# LCD.net
KiCad netlist of a schematic drawn in Altium Designer
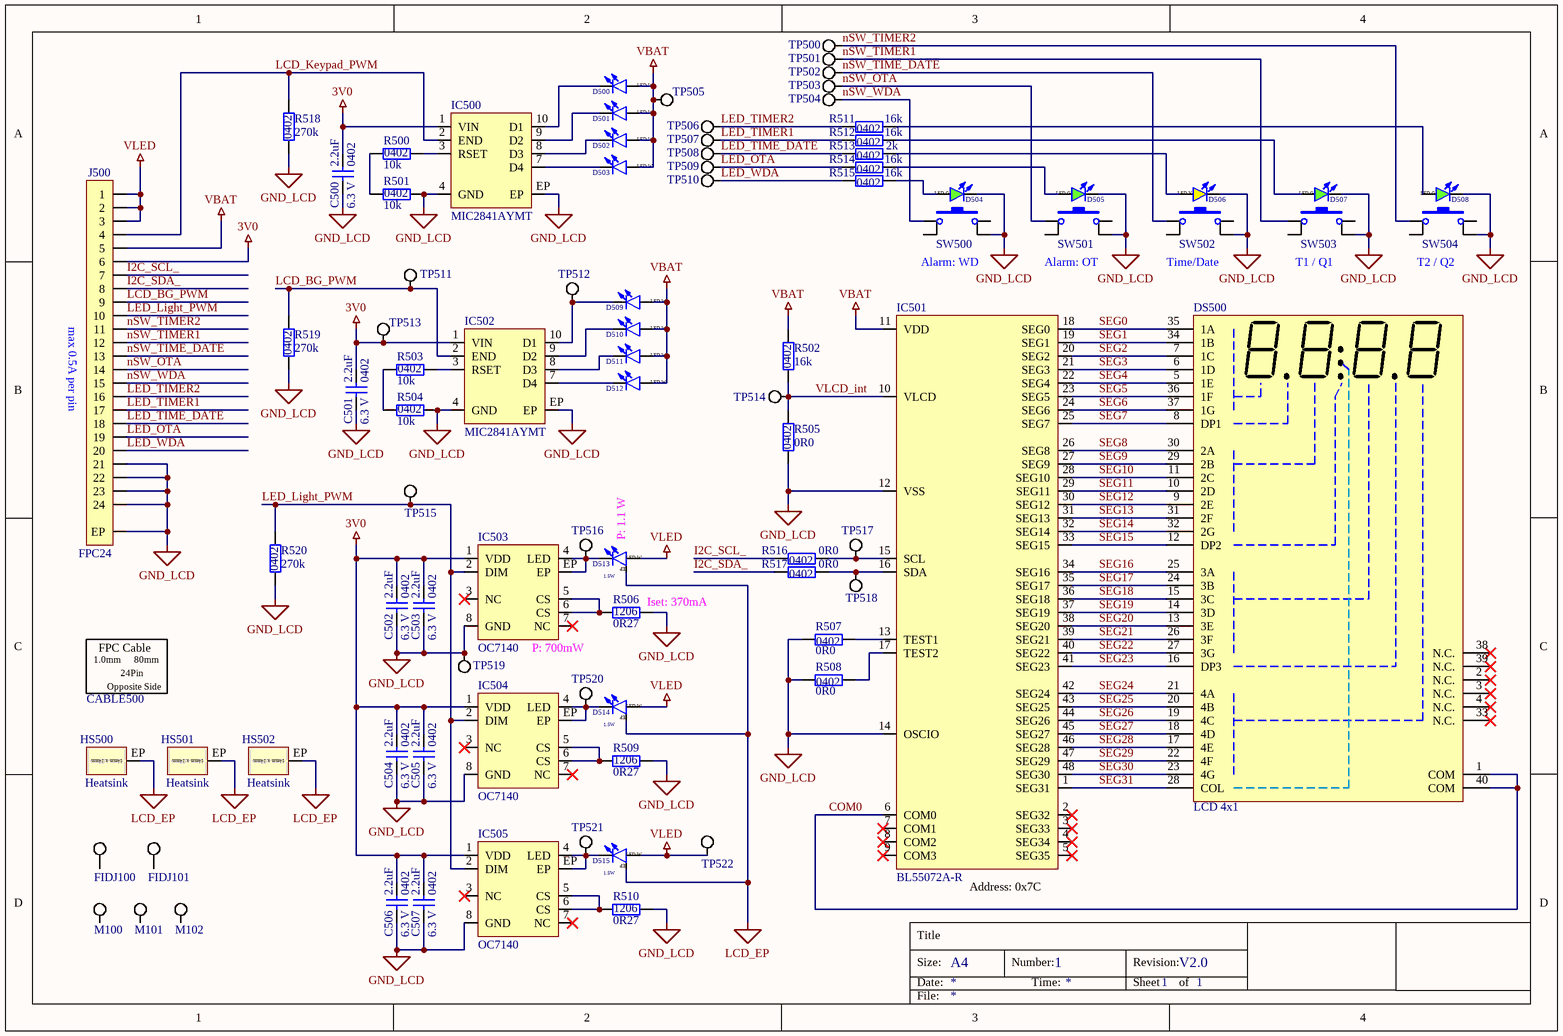
[diagram p0: LCD.SchDoc]

(export (version "E")
  (design (tool "Eeschema 10.0.6"))
  (components
    (comp (ref "C500")
      (value "C 2.2uF 0402 6.3V")
      (footprint "0402")
      (description "CAP CER 2.2UF 6.3V X6T 0402")
      (fields
        (field (name "MANUFACTURER") "Murata Electronics")
        (field (name "MANUFACTURER PART NUMBER") "GRM155D80J225ME95D")
        (field (name "CAPACITANCE") "2.2uF")
        (field (name "VOLTAGE") "6.3 V")
      )
      (libsource (lib "CS_Part_Library") (part "CAP_2.2uF_6V3_0402"))
    )
    (comp (ref "C501")
      (value "C 2.2uF 0402 6.3V")
      (footprint "0402")
      (description "CAP CER 2.2UF 6.3V X6T 0402")
      (fields
        (field (name "MANUFACTURER") "Murata Electronics")
        (field (name "MANUFACTURER PART NUMBER") "GRM155D80J225ME95D")
        (field (name "CAPACITANCE") "2.2uF")
        (field (name "VOLTAGE") "6.3 V")
      )
      (libsource (lib "CS_Part_Library") (part "CAP_2.2uF_6V3_0402"))
    )
    (comp (ref "C502")
      (value "C 2.2uF 0402 6.3V")
      (footprint "0402")
      (description "CAP CER 2.2UF 6.3V X6T 0402")
      (fields
        (field (name "MANUFACTURER") "Murata Electronics")
        (field (name "MANUFACTURER PART NUMBER") "GRM155D80J225ME95D")
        (field (name "CAPACITANCE") "2.2uF")
        (field (name "VOLTAGE") "6.3 V")
      )
      (libsource (lib "CS_Part_Library") (part "CAP_2.2uF_6V3_0402"))
    )
    (comp (ref "C503")
      (value "C 2.2uF 0402 6.3V")
      (footprint "0402")
      (description "CAP CER 2.2UF 6.3V X6T 0402")
      (fields
        (field (name "MANUFACTURER") "Murata Electronics")
        (field (name "MANUFACTURER PART NUMBER") "GRM155D80J225ME95D")
        (field (name "CAPACITANCE") "2.2uF")
        (field (name "VOLTAGE") "6.3 V")
      )
      (libsource (lib "CS_Part_Library") (part "CAP_2.2uF_6V3_0402"))
    )
    (comp (ref "C504")
      (value "C 2.2uF 0402 6.3V")
      (footprint "0402")
      (description "CAP CER 2.2UF 6.3V X6T 0402")
      (fields
        (field (name "MANUFACTURER") "Murata Electronics")
        (field (name "MANUFACTURER PART NUMBER") "GRM155D80J225ME95D")
        (field (name "CAPACITANCE") "2.2uF")
        (field (name "VOLTAGE") "6.3 V")
      )
      (libsource (lib "CS_Part_Library") (part "CAP_2.2uF_6V3_0402"))
    )
    (comp (ref "C505")
      (value "C 2.2uF 0402 6.3V")
      (footprint "0402")
      (description "CAP CER 2.2UF 6.3V X6T 0402")
      (fields
        (field (name "MANUFACTURER") "Murata Electronics")
        (field (name "MANUFACTURER PART NUMBER") "GRM155D80J225ME95D")
        (field (name "CAPACITANCE") "2.2uF")
        (field (name "VOLTAGE") "6.3 V")
      )
      (libsource (lib "CS_Part_Library") (part "CAP_2.2uF_6V3_0402"))
    )
    (comp (ref "C506")
      (value "C 2.2uF 0402 6.3V")
      (footprint "0402")
      (description "CAP CER 2.2UF 6.3V X6T 0402")
      (fields
        (field (name "MANUFACTURER") "Murata Electronics")
        (field (name "MANUFACTURER PART NUMBER") "GRM155D80J225ME95D")
        (field (name "CAPACITANCE") "2.2uF")
        (field (name "VOLTAGE") "6.3 V")
      )
      (libsource (lib "CS_Part_Library") (part "CAP_2.2uF_6V3_0402"))
    )
    (comp (ref "C507")
      (value "C 2.2uF 0402 6.3V")
      (footprint "0402")
      (description "CAP CER 2.2UF 6.3V X6T 0402")
      (fields
        (field (name "MANUFACTURER") "Murata Electronics")
        (field (name "MANUFACTURER PART NUMBER") "GRM155D80J225ME95D")
        (field (name "CAPACITANCE") "2.2uF")
        (field (name "VOLTAGE") "6.3 V")
      )
      (libsource (lib "CS_Part_Library") (part "CAP_2.2uF_6V3_0402"))
    )
    (comp (ref "CABLE500")
      (value "FPC24p80mm")
      (description "FPC Cable 1mm Pitch 24Pin 80mm Opposite Sides")
      (fields
        (field (name "MANUFACTURER") "LX")
        (field (name "MANUFACTURER PART NUMBER") "C50299")
        (field (name "PITCH") "1.0mm")
        (field (name "LENGTH") "80mm")
        (field (name "MODE") "Opposite Side")
        (field (name "NOOFPINS") "24Pin")
      )
      (libsource (lib "Symbols") (part "CABLE_FPC24_80"))
    )
    (comp (ref "D500")
      (value "LED W")
      (footprint "LED_99-218UMC_side")
      (description "LED WHITE SIDE SMD")
      (fields
        (field (name "MANUFACTURER") "Everlight Elec")
        (field (name "MANUFACTURER PART NUMBER") "99-218UMC/1637CD/TR8-T")
      )
      (libsource (lib "Symbols") (part "D_LED_White_s"))
    )
    (comp (ref "D501")
      (value "LED W")
      (footprint "LED_99-218UMC_side")
      (description "LED WHITE SIDE SMD")
      (fields
        (field (name "MANUFACTURER") "Everlight Elec")
        (field (name "MANUFACTURER PART NUMBER") "99-218UMC/1637CD/TR8-T")
      )
      (libsource (lib "Symbols") (part "D_LED_White_s"))
    )
    (comp (ref "D502")
      (value "LED W")
      (footprint "LED_99-218UMC_side")
      (description "LED WHITE SIDE SMD")
      (fields
        (field (name "MANUFACTURER") "Everlight Elec")
        (field (name "MANUFACTURER PART NUMBER") "99-218UMC/1637CD/TR8-T")
      )
      (libsource (lib "Symbols") (part "D_LED_White_s"))
    )
    (comp (ref "D503")
      (value "LED W")
      (footprint "LED_99-218UMC_side")
      (description "LED WHITE SIDE SMD")
      (fields
        (field (name "MANUFACTURER") "Everlight Elec")
        (field (name "MANUFACTURER PART NUMBER") "99-218UMC/1637CD/TR8-T")
      )
      (libsource (lib "Symbols") (part "D_LED_White_s"))
    )
    (comp (ref "D504")
      (value "LED G")
      (footprint "LED_0603")
      (description "LED GREEN DIFFUSED 0603 SMD")
      (fields
        (field (name "MANUFACTURER") "OSRAM Opto Semiconductors Inc.")
        (field (name "MANUFACTURER PART NUMBER") "LT Q39G-Q1OO-25-1")
      )
      (libsource (lib "CS_Part_Library") (part "D_LED_Green_0603"))
    )
    (comp (ref "D505")
      (value "LED G")
      (footprint "LED_0603")
      (description "LED GREEN DIFFUSED 0603 SMD")
      (fields
        (field (name "MANUFACTURER") "OSRAM Opto Semiconductors Inc.")
        (field (name "MANUFACTURER PART NUMBER") "LT Q39G-Q1OO-25-1")
      )
      (libsource (lib "CS_Part_Library") (part "D_LED_Green_0603"))
    )
    (comp (ref "D506")
      (value "LED Y")
      (footprint "LED_0603")
      (description "LED YELLOW DIFFUSED")
      (fields
        (field (name "MANUFACTURER") "Stanley Electric Co")
        (field (name "MANUFACTURER PART NUMBER") "FKY1111C-TR")
      )
      (libsource (lib "CS_Part_Library") (part "D_LED_Yellow_0603"))
    )
    (comp (ref "D507")
      (value "LED G")
      (footprint "LED_0603")
      (description "LED GREEN DIFFUSED 0603 SMD")
      (fields
        (field (name "MANUFACTURER") "OSRAM Opto Semiconductors Inc.")
        (field (name "MANUFACTURER PART NUMBER") "LT Q39G-Q1OO-25-1")
      )
      (libsource (lib "CS_Part_Library") (part "D_LED_Green_0603"))
    )
    (comp (ref "D508")
      (value "LED G")
      (footprint "LED_0603")
      (description "LED GREEN DIFFUSED 0603 SMD")
      (fields
        (field (name "MANUFACTURER") "OSRAM Opto Semiconductors Inc.")
        (field (name "MANUFACTURER PART NUMBER") "LT Q39G-Q1OO-25-1")
      )
      (libsource (lib "CS_Part_Library") (part "D_LED_Green_0603"))
    )
    (comp (ref "D509")
      (value "LED W")
      (footprint "LED_99-218UMC_side")
      (description "LED WHITE SIDE SMD")
      (fields
        (field (name "MANUFACTURER") "Everlight Elec")
        (field (name "MANUFACTURER PART NUMBER") "99-218UMC/1637CD/TR8-T")
      )
      (libsource (lib "Symbols") (part "D_LED_White_s"))
    )
    (comp (ref "D510")
      (value "LED W")
      (footprint "LED_99-218UMC_side")
      (description "LED WHITE SIDE SMD")
      (fields
        (field (name "MANUFACTURER") "Everlight Elec")
        (field (name "MANUFACTURER PART NUMBER") "99-218UMC/1637CD/TR8-T")
      )
      (libsource (lib "Symbols") (part "D_LED_White_s"))
    )
    (comp (ref "D511")
      (value "LED W")
      (footprint "LED_99-218UMC_side")
      (description "LED WHITE SIDE SMD")
      (fields
        (field (name "MANUFACTURER") "Everlight Elec")
        (field (name "MANUFACTURER PART NUMBER") "99-218UMC/1637CD/TR8-T")
      )
      (libsource (lib "Symbols") (part "D_LED_White_s"))
    )
    (comp (ref "D512")
      (value "LED W")
      (footprint "LED_99-218UMC_side")
      (description "LED WHITE SIDE SMD")
      (fields
        (field (name "MANUFACTURER") "Everlight Elec")
        (field (name "MANUFACTURER PART NUMBER") "99-218UMC/1637CD/TR8-T")
      )
      (libsource (lib "Symbols") (part "D_LED_White_s"))
    )
    (comp (ref "D513")
      (value "LED W")
      (footprint "LED_3.3x3.3_ThermalVia")
      (description "LED XLAMP WARM WHT 2700K SMD")
      (fields
        (field (name "MANUFACTURER") "CreeLED, Inc.")
        (field (name "MANUFACTURER PART NUMBER") "XTEAWT-E0-0000-00000HEE8")
        (field (name "POWER") "1.5W")
      )
      (libsource (lib "CS_Part_Library") (part "D_LED_W_HP_3"))
    )
    (comp (ref "D514")
      (value "LED W")
      (footprint "LED_3.3x3.3_ThermalVia")
      (description "LED XLAMP WARM WHT 2700K SMD")
      (fields
        (field (name "MANUFACTURER") "CreeLED, Inc.")
        (field (name "MANUFACTURER PART NUMBER") "XTEAWT-E0-0000-00000HEE8")
        (field (name "POWER") "1.5W")
      )
      (libsource (lib "CS_Part_Library") (part "D_LED_W_HP_3"))
    )
    (comp (ref "D515")
      (value "LED W")
      (footprint "LED_3.3x3.3_ThermalVia")
      (description "LED XLAMP WARM WHT 2700K SMD")
      (fields
        (field (name "MANUFACTURER") "CreeLED, Inc.")
        (field (name "MANUFACTURER PART NUMBER") "XTEAWT-E0-0000-00000HEE8")
        (field (name "POWER") "1.5W")
      )
      (libsource (lib "CS_Part_Library") (part "D_LED_W_HP_3"))
    )
    (comp (ref "DS500")
      (value "LCD 4x1")
      (footprint "DISPL_7SEG_4")
      (description "LCD MOD 4 DIG 4 X 1 REFLECTIVE")
      (fields
        (field (name "MANUFACTURER") "Varitronix")
        (field (name "MANUFACTURER PART NUMBER") "VI-402-DP-RC-S")
      )
      (libsource (lib "Symbols") (part "DISPL_7SEG_4x1"))
    )
    (comp (ref "FIDJ100")
      (value "Fiducial")
      (footprint "FIDJ_1mm")
      (description "Fiducal 1mm")
      (libsource (lib "CS_Part_Library") (part "FIDJ_1mm"))
    )
    (comp (ref "FIDJ101")
      (value "Fiducial")
      (footprint "FIDJ_1mm")
      (description "Fiducal 1mm")
      (libsource (lib "CS_Part_Library") (part "FIDJ_1mm"))
    )
    (comp (ref "HS500")
      (value "Heatsink")
      (footprint "Heatsink_Alphacool17425")
      (description "Heatsink 6.5mm x 6.5mm")
      (fields (field (name "MANUFACTURER") "Alphacool") (field (name "MANUFACTURER PART NUMBER") "17425"))
      (libsource (lib "Symbols") (part "Heatsink_6.5x6.5"))
    )
    (comp (ref "HS501")
      (value "Heatsink")
      (footprint "Heatsink_Alphacool17425")
      (description "Heatsink 6.5mm x 6.5mm")
      (fields (field (name "MANUFACTURER") "Alphacool") (field (name "MANUFACTURER PART NUMBER") "17425"))
      (libsource (lib "Symbols") (part "Heatsink_6.5x6.5"))
    )
    (comp (ref "HS502")
      (value "Heatsink")
      (footprint "Heatsink_Alphacool17425")
      (description "Heatsink 6.5mm x 6.5mm")
      (fields (field (name "MANUFACTURER") "Alphacool") (field (name "MANUFACTURER PART NUMBER") "17425"))
      (libsource (lib "Symbols") (part "Heatsink_6.5x6.5"))
    )
    (comp (ref "IC500")
      (value "MIC2841AYMT")
      (footprint "UFDFN-10")
      (description "IC LED DRIVER 4 CH")
      (fields
        (field (name "MANUFACTURER") "Microchip Technology")
        (field (name "MANUFACTURER PART NUMBER") "MIC2841AYMT-TR")
      )
      (libsource (lib "CS_Part_Library") (part "IC_LED_cntr_MIC2841"))
    )
    (comp (ref "IC501")
      (value "BL55072A-R")
      (footprint "TSSOP-48")
      (description "IC LCD DRIVER 36SEG TSSOP-48")
      (fields (field (name "MANUFACTURER") "BL(Shanghai Belling)"))
      (libsource (lib "Symbols") (part "IC_LCD_cntr_BL55072A-R"))
    )
    (comp (ref "IC502")
      (value "MIC2841AYMT")
      (footprint "UFDFN-10")
      (description "IC LED DRIVER 4 CH")
      (fields
        (field (name "MANUFACTURER") "Microchip Technology")
        (field (name "MANUFACTURER PART NUMBER") "MIC2841AYMT-TR")
      )
      (libsource (lib "CS_Part_Library") (part "IC_LED_cntr_MIC2841"))
    )
    (comp (ref "IC503")
      (value "OC7140")
      (footprint "SOIC-8-EP")
      (description "IC LED DRIVER 1 CH 2A ESOP8")
      (fields (field (name "MANUFACTURER") "OCX"))
      (libsource (lib "Symbols") (part "IC_LED_cntr_OC7140"))
    )
    (comp (ref "IC504")
      (value "OC7140")
      (footprint "SOIC-8-EP")
      (description "IC LED DRIVER 1 CH 2A ESOP8")
      (fields (field (name "MANUFACTURER") "OCX"))
      (libsource (lib "Symbols") (part "IC_LED_cntr_OC7140"))
    )
    (comp (ref "IC505")
      (value "OC7140")
      (footprint "SOIC-8-EP")
      (description "IC LED DRIVER 1 CH 2A ESOP8")
      (fields (field (name "MANUFACTURER") "OCX"))
      (libsource (lib "Symbols") (part "IC_LED_cntr_OC7140"))
    )
    (comp (ref "J500")
      (value "FPC24")
      (footprint "J_FPC_522712479")
      (description "CONN FPC BOT 24 PIN 1mm Pitch")
      (fields (field (name "MANUFACTURER") "MOLEX") (field (name "MANUFACTURER PART NUMBER") "522712479"))
      (libsource (lib "Symbols") (part "J_FPC24_DS"))
    )
    (comp (ref "M100")
      (value "M3x8")
      (footprint "SCREW_M3x8_nP_FH")
      (description "Skrew M3x8 Not Plated Flathat")
      (libsource (lib "CS_Part_Library") (part "SCREW_M3x8_nP_FH"))
    )
    (comp (ref "M101")
      (value "M3x8")
      (footprint "SCREW_M3x8_nP_FH")
      (description "Skrew M3x8 Not Plated Flathat")
      (libsource (lib "CS_Part_Library") (part "SCREW_M3x8_nP_FH"))
    )
    (comp (ref "M102")
      (value "M3x8")
      (footprint "SCREW_M3x8_nP_FH")
      (description "Skrew M3x8 Not Plated Flathat")
      (libsource (lib "CS_Part_Library") (part "SCREW_M3x8_nP_FH"))
    )
    (comp (ref "R500")
      (value "R 10k 0402")
      (footprint "0402")
      (description "RES 10K OHM 1% 1/16W 0402")
      (fields
        (field (name "MANUFACTURER") "YAGEO")
        (field (name "MANUFACTURER PART NUMBER") "RC0402FR-0710KL")
        (field (name "RESISTANCE") "10k")
      )
      (libsource (lib "CS_Part_Library") (part "R_10k_0402"))
    )
    (comp (ref "R501")
      (value "R 10k 0402")
      (footprint "0402")
      (description "RES 10K OHM 1% 1/16W 0402")
      (fields
        (field (name "MANUFACTURER") "YAGEO")
        (field (name "MANUFACTURER PART NUMBER") "RC0402FR-0710KL")
        (field (name "RESISTANCE") "10k")
      )
      (libsource (lib "CS_Part_Library") (part "R_10k_0402"))
    )
    (comp (ref "R502")
      (value "R 16k 0402")
      (footprint "0402")
      (description "RES 16K OHM 1% 1/16W 0402")
      (fields
        (field (name "MANUFACTURER") "Stackpole Electronics Inc")
        (field (name "MANUFACTURER PART NUMBER") "RMCF0402FT16K0")
        (field (name "RESISTANCE") "16k")
      )
      (libsource (lib "") (part "R_16k_0402_1"))
    )
    (comp (ref "R503")
      (value "R 10k 0402")
      (footprint "0402")
      (description "RES 10K OHM 1% 1/16W 0402")
      (fields
        (field (name "MANUFACTURER") "YAGEO")
        (field (name "MANUFACTURER PART NUMBER") "RC0402FR-0710KL")
        (field (name "RESISTANCE") "10k")
      )
      (libsource (lib "CS_Part_Library") (part "R_10k_0402"))
    )
    (comp (ref "R504")
      (value "R 10k 0402")
      (footprint "0402")
      (description "RES 10K OHM 1% 1/16W 0402")
      (fields
        (field (name "MANUFACTURER") "YAGEO")
        (field (name "MANUFACTURER PART NUMBER") "RC0402FR-0710KL")
        (field (name "RESISTANCE") "10k")
      )
      (libsource (lib "CS_Part_Library") (part "R_10k_0402"))
    )
    (comp (ref "R505")
      (value "R 0R0 0402")
      (footprint "0402")
      (description "RES 0 OHM JUMPER 1/16W 0402")
      (fields
        (field (name "MANUFACTURER") "Stackpole Electronics Inc")
        (field (name "MANUFACTURER PART NUMBER") "RMCF0402ZT0R00")
        (field (name "RESISTANCE") "0R0")
      )
      (libsource (lib "") (part "R_0R0_0402_1"))
    )
    (comp (ref "R506")
      (value "R 0R27 1206")
      (footprint "1206")
      (description "RES 0.27 OHM 1% 1/3W 1206")
      (fields
        (field (name "MANUFACTURER") "RALEC")
        (field (name "MANUFACTURER PART NUMBER") "RTT06R270FTP")
        (field (name "RESISTANCE") "0R27")
      )
      (libsource (lib "Symbols") (part "R_0R27_1206"))
    )
    (comp (ref "R507")
      (value "R 0R0 0402")
      (footprint "0402")
      (description "RES 0 OHM JUMPER 1/16W 0402")
      (fields
        (field (name "MANUFACTURER") "Stackpole Electronics Inc")
        (field (name "MANUFACTURER PART NUMBER") "RMCF0402ZT0R00")
        (field (name "RESISTANCE") "0R0")
      )
      (libsource (lib "CS_Part_Library") (part "R_0R0_0402"))
    )
    (comp (ref "R508")
      (value "R 0R0 0402")
      (footprint "0402")
      (description "RES 0 OHM JUMPER 1/16W 0402")
      (fields
        (field (name "MANUFACTURER") "Stackpole Electronics Inc")
        (field (name "MANUFACTURER PART NUMBER") "RMCF0402ZT0R00")
        (field (name "RESISTANCE") "0R0")
      )
      (libsource (lib "CS_Part_Library") (part "R_0R0_0402"))
    )
    (comp (ref "R509")
      (value "R 0R27 1206")
      (footprint "1206")
      (description "RES 0.27 OHM 1% 1/3W 1206")
      (fields
        (field (name "MANUFACTURER") "RALEC")
        (field (name "MANUFACTURER PART NUMBER") "RTT06R270FTP")
        (field (name "RESISTANCE") "0R27")
      )
      (libsource (lib "Symbols") (part "R_0R27_1206"))
    )
    (comp (ref "R510")
      (value "R 0R27 1206")
      (footprint "1206")
      (description "RES 0.27 OHM 1% 1/3W 1206")
      (fields
        (field (name "MANUFACTURER") "RALEC")
        (field (name "MANUFACTURER PART NUMBER") "RTT06R270FTP")
        (field (name "RESISTANCE") "0R27")
      )
      (libsource (lib "Symbols") (part "R_0R27_1206"))
    )
    (comp (ref "R511")
      (value "R 16k 0402")
      (footprint "0402")
      (description "RES 16K OHM 1% 1/16W 0402")
      (fields
        (field (name "MANUFACTURER") "Stackpole Electronics Inc")
        (field (name "MANUFACTURER PART NUMBER") "RMCF0402FT16K0")
        (field (name "RESISTANCE") "16k")
      )
      (libsource (lib "CS_Part_Library") (part "R_16k_0402"))
    )
    (comp (ref "R512")
      (value "R 16k 0402")
      (footprint "0402")
      (description "RES 16K OHM 1% 1/16W 0402")
      (fields
        (field (name "MANUFACTURER") "Stackpole Electronics Inc")
        (field (name "MANUFACTURER PART NUMBER") "RMCF0402FT16K0")
        (field (name "RESISTANCE") "16k")
      )
      (libsource (lib "CS_Part_Library") (part "R_16k_0402"))
    )
    (comp (ref "R513")
      (value "R 2k 0402")
      (footprint "0402")
      (description "RES 2K OHM 1% 1/16W 0402")
      (fields
        (field (name "MANUFACTURER") "Stackpole Electronics Inc")
        (field (name "MANUFACTURER PART NUMBER") "RMCF0402FT2K00")
        (field (name "RESISTANCE") "2k")
      )
      (libsource (lib "CS_Part_Library") (part "R_2k_0402"))
    )
    (comp (ref "R514")
      (value "R 16k 0402")
      (footprint "0402")
      (description "RES 16K OHM 1% 1/16W 0402")
      (fields
        (field (name "MANUFACTURER") "Stackpole Electronics Inc")
        (field (name "MANUFACTURER PART NUMBER") "RMCF0402FT16K0")
        (field (name "RESISTANCE") "16k")
      )
      (libsource (lib "CS_Part_Library") (part "R_16k_0402"))
    )
    (comp (ref "R515")
      (value "R 16k 0402")
      (footprint "0402")
      (description "RES 16K OHM 1% 1/16W 0402")
      (fields
        (field (name "MANUFACTURER") "Stackpole Electronics Inc")
        (field (name "MANUFACTURER PART NUMBER") "RMCF0402FT16K0")
        (field (name "RESISTANCE") "16k")
      )
      (libsource (lib "CS_Part_Library") (part "R_16k_0402"))
    )
    (comp (ref "R516")
      (value "R 0R0 0402")
      (footprint "0402")
      (description "RES 0 OHM JUMPER 1/16W 0402")
      (fields
        (field (name "MANUFACTURER") "Stackpole Electronics Inc")
        (field (name "MANUFACTURER PART NUMBER") "RMCF0402ZT0R00")
        (field (name "RESISTANCE") "0R0")
      )
      (libsource (lib "CS_Part_Library") (part "R_0R0_0402"))
    )
    (comp (ref "R517")
      (value "R 0R0 0402")
      (footprint "0402")
      (description "RES 0 OHM JUMPER 1/16W 0402")
      (fields
        (field (name "MANUFACTURER") "Stackpole Electronics Inc")
        (field (name "MANUFACTURER PART NUMBER") "RMCF0402ZT0R00")
        (field (name "RESISTANCE") "0R0")
      )
      (libsource (lib "CS_Part_Library") (part "R_0R0_0402"))
    )
    (comp (ref "R518")
      (value "R 270k 0402")
      (footprint "0402")
      (description "RES 270K OHM 1% 1/16W 0402")
      (fields
        (field (name "MANUFACTURER") "YAGEO")
        (field (name "MANUFACTURER PART NUMBER") "RC0402FR-07270KL")
        (field (name "RESISTANCE") "270k")
      )
      (libsource (lib "CS_Part_Library") (part "R_270k_0402"))
    )
    (comp (ref "R519")
      (value "R 270k 0402")
      (footprint "0402")
      (description "RES 270K OHM 1% 1/16W 0402")
      (fields
        (field (name "MANUFACTURER") "YAGEO")
        (field (name "MANUFACTURER PART NUMBER") "RC0402FR-07270KL")
        (field (name "RESISTANCE") "270k")
      )
      (libsource (lib "CS_Part_Library") (part "R_270k_0402"))
    )
    (comp (ref "R520")
      (value "R 270k 0402")
      (footprint "0402")
      (description "RES 270K OHM 1% 1/16W 0402")
      (fields
        (field (name "MANUFACTURER") "YAGEO")
        (field (name "MANUFACTURER PART NUMBER") "RC0402FR-07270KL")
        (field (name "RESISTANCE") "270k")
      )
      (libsource (lib "CS_Part_Library") (part "R_270k_0402"))
    )
    (comp (ref "SW500")
      (value "SW")
      (footprint "SW_BRIGHT_6.1x6.1")
      (description "SWITCH TACTILE SW-SMD")
      (fields
        (field (name "MANUFACTURER") "BRIGHT")
        (field (name "MANUFACTURER PART NUMBER") "TSA063G50-250")
      )
      (libsource (lib "CS_Part_Library") (part "SW_TactileSW_V_2"))
    )
    (comp (ref "SW501")
      (value "SW")
      (footprint "SW_BRIGHT_6.1x6.1")
      (description "SWITCH TACTILE SW-SMD")
      (fields
        (field (name "MANUFACTURER") "BRIGHT")
        (field (name "MANUFACTURER PART NUMBER") "TSA063G50-250")
      )
      (libsource (lib "CS_Part_Library") (part "SW_TactileSW_V_2"))
    )
    (comp (ref "SW502")
      (value "SW")
      (footprint "SW_BRIGHT_6.1x6.1")
      (description "SWITCH TACTILE SW-SMD")
      (fields
        (field (name "MANUFACTURER") "BRIGHT")
        (field (name "MANUFACTURER PART NUMBER") "TSA063G50-250")
      )
      (libsource (lib "CS_Part_Library") (part "SW_TactileSW_V_2"))
    )
    (comp (ref "SW503")
      (value "SW")
      (footprint "SW_BRIGHT_6.1x6.1")
      (description "SWITCH TACTILE SW-SMD")
      (fields
        (field (name "MANUFACTURER") "BRIGHT")
        (field (name "MANUFACTURER PART NUMBER") "TSA063G50-250")
      )
      (libsource (lib "CS_Part_Library") (part "SW_TactileSW_V_2"))
    )
    (comp (ref "SW504")
      (value "SW")
      (footprint "SW_BRIGHT_6.1x6.1")
      (description "SWITCH TACTILE SW-SMD")
      (fields
        (field (name "MANUFACTURER") "BRIGHT")
        (field (name "MANUFACTURER PART NUMBER") "TSA063G50-250")
      )
      (libsource (lib "CS_Part_Library") (part "SW_TactileSW_V_2"))
    )
    (comp (ref "TP500")
      (value "TP")
      (footprint "TP_1mm")
      (description "Test Point 1mm")
      (libsource (lib "CS_Part_Library") (part "TP_1mm"))
    )
    (comp (ref "TP501")
      (value "TP")
      (footprint "TP_1mm")
      (description "Test Point 1mm")
      (libsource (lib "CS_Part_Library") (part "TP_1mm"))
    )
    (comp (ref "TP502")
      (value "TP")
      (footprint "TP_1mm")
      (description "Test Point 1mm")
      (libsource (lib "CS_Part_Library") (part "TP_1mm"))
    )
    (comp (ref "TP503")
      (value "TP")
      (footprint "TP_1mm")
      (description "Test Point 1mm")
      (libsource (lib "CS_Part_Library") (part "TP_1mm"))
    )
    (comp (ref "TP504")
      (value "TP")
      (footprint "TP_1mm")
      (description "Test Point 1mm")
      (libsource (lib "CS_Part_Library") (part "TP_1mm"))
    )
    (comp (ref "TP505")
      (value "TP")
      (footprint "TP_1mm")
      (description "Test Point 1mm")
      (libsource (lib "CS_Part_Library") (part "TP_1mm"))
    )
    (comp (ref "TP506")
      (value "TP")
      (footprint "TP_1mm")
      (description "Test Point 1mm")
      (libsource (lib "CS_Part_Library") (part "TP_1mm"))
    )
    (comp (ref "TP507")
      (value "TP")
      (footprint "TP_1mm")
      (description "Test Point 1mm")
      (libsource (lib "CS_Part_Library") (part "TP_1mm"))
    )
    (comp (ref "TP508")
      (value "TP")
      (footprint "TP_1mm")
      (description "Test Point 1mm")
      (libsource (lib "CS_Part_Library") (part "TP_1mm"))
    )
    (comp (ref "TP509")
      (value "TP")
      (footprint "TP_1mm")
      (description "Test Point 1mm")
      (libsource (lib "CS_Part_Library") (part "TP_1mm"))
    )
    (comp (ref "TP510")
      (value "TP")
      (footprint "TP_1mm")
      (description "Test Point 1mm")
      (libsource (lib "CS_Part_Library") (part "TP_1mm"))
    )
    (comp (ref "TP511")
      (value "TP")
      (footprint "TP_1mm")
      (description "Test Point 1mm")
      (libsource (lib "CS_Part_Library") (part "TP_1mm"))
    )
    (comp (ref "TP512")
      (value "TP")
      (footprint "TP_1mm")
      (description "Test Point 1mm")
      (libsource (lib "CS_Part_Library") (part "TP_1mm"))
    )
    (comp (ref "TP513")
      (value "TP")
      (footprint "TP_1mm")
      (description "Test Point 1mm")
      (libsource (lib "CS_Part_Library") (part "TP_1mm"))
    )
    (comp (ref "TP514")
      (value "TP")
      (footprint "TP_1mm")
      (description "Test Point 1mm")
      (libsource (lib "CS_Part_Library") (part "TP_1mm"))
    )
    (comp (ref "TP515")
      (value "TP")
      (footprint "TP_1mm")
      (description "Test Point 1mm")
      (libsource (lib "CS_Part_Library") (part "TP_1mm"))
    )
    (comp (ref "TP516")
      (value "TP")
      (footprint "TP_1mm")
      (description "Test Point 1mm")
      (libsource (lib "CS_Part_Library") (part "TP_1mm"))
    )
    (comp (ref "TP517")
      (value "TP")
      (footprint "TP_1mm")
      (description "Test Point 1mm")
      (libsource (lib "CS_Part_Library") (part "TP_1mm"))
    )
    (comp (ref "TP518")
      (value "TP")
      (footprint "TP_1mm")
      (description "Test Point 1mm")
      (libsource (lib "CS_Part_Library") (part "TP_1mm"))
    )
    (comp (ref "TP519")
      (value "TP")
      (footprint "TP_1mm")
      (description "Test Point 1mm")
      (libsource (lib "CS_Part_Library") (part "TP_1mm"))
    )
    (comp (ref "TP520")
      (value "TP")
      (footprint "TP_1mm")
      (description "Test Point 1mm")
      (libsource (lib "CS_Part_Library") (part "TP_1mm"))
    )
    (comp (ref "TP521")
      (value "TP")
      (footprint "TP_1mm")
      (description "Test Point 1mm")
      (libsource (lib "CS_Part_Library") (part "TP_1mm"))
    )
    (comp (ref "TP522")
      (value "TP")
      (footprint "TP_1mm")
      (description "Test Point 1mm")
      (libsource (lib "CS_Part_Library") (part "TP_1mm"))
    )
  )
  (nets
    (net (code "1") (name "/COM0") (class "Default")
      (node (ref "DS500") (pin "1") (pinfunction "COM_1") (pintype "passive"))
      (node (ref "DS500") (pin "40") (pinfunction "COM_40") (pintype "passive"))
      (node (ref "IC501") (pin "6") (pinfunction "COM0_6") (pintype "passive"))
    )
    (net (code "2") (name "/I2C_SCL_") (class "Default")
      (node (ref "J500") (pin "7") (pinfunction "7_7") (pintype "passive"))
      (node (ref "R516") (pin "2") (pinfunction "2_2") (pintype "passive"))
    )
    (net (code "3") (name "/I2C_SDA_") (class "Default")
      (node (ref "J500") (pin "8") (pinfunction "8_8") (pintype "passive"))
      (node (ref "R517") (pin "2") (pinfunction "2_2") (pintype "passive"))
    )
    (net (code "4") (name "/LCD_BG_PWM") (class "Default")
      (node (ref "IC502") (pin "2") (pinfunction "END_2") (pintype "passive"))
      (node (ref "J500") (pin "9") (pinfunction "9_9") (pintype "passive"))
      (node (ref "R519") (pin "2") (pinfunction "2_2") (pintype "passive"))
      (node (ref "TP511") (pin "1") (pinfunction "TP_1") (pintype "passive"))
    )
    (net (code "5") (name "/LCD_Keypad_PWM") (class "Default")
      (node (ref "IC500") (pin "2") (pinfunction "END_2") (pintype "passive"))
      (node (ref "J500") (pin "4") (pinfunction "4_4") (pintype "passive"))
      (node (ref "R518") (pin "2") (pinfunction "2_2") (pintype "passive"))
    )
    (net (code "6") (name "/LED_Light_PWM") (class "Default")
      (node (ref "IC503") (pin "2") (pinfunction "DIM_2") (pintype "passive"))
      (node (ref "IC504") (pin "2") (pinfunction "DIM_2") (pintype "passive"))
      (node (ref "IC505") (pin "2") (pinfunction "DIM_2") (pintype "passive"))
      (node (ref "J500") (pin "10") (pinfunction "10_10") (pintype "passive"))
      (node (ref "R520") (pin "2") (pinfunction "2_2") (pintype "passive"))
      (node (ref "TP515") (pin "1") (pinfunction "TP_1") (pintype "passive"))
    )
    (net (code "7") (name "/LED_OTA") (class "Default")
      (node (ref "J500") (pin "19") (pinfunction "19_19") (pintype "passive"))
      (node (ref "R514") (pin "2") (pinfunction "2_2") (pintype "passive"))
      (node (ref "TP509") (pin "1") (pinfunction "TP_1") (pintype "passive"))
    )
    (net (code "8") (name "/LED_TIMER1") (class "Default")
      (node (ref "J500") (pin "17") (pinfunction "17_17") (pintype "passive"))
      (node (ref "R512") (pin "2") (pinfunction "2_2") (pintype "passive"))
      (node (ref "TP507") (pin "1") (pinfunction "TP_1") (pintype "passive"))
    )
    (net (code "9") (name "/LED_TIMER2") (class "Default")
      (node (ref "J500") (pin "16") (pinfunction "16_16") (pintype "passive"))
      (node (ref "R511") (pin "2") (pinfunction "2_2") (pintype "passive"))
      (node (ref "TP506") (pin "1") (pinfunction "TP_1") (pintype "passive"))
    )
    (net (code "10") (name "/LED_TIME_DATE") (class "Default")
      (node (ref "J500") (pin "18") (pinfunction "18_18") (pintype "passive"))
      (node (ref "R513") (pin "2") (pinfunction "2_2") (pintype "passive"))
      (node (ref "TP508") (pin "1") (pinfunction "TP_1") (pintype "passive"))
    )
    (net (code "11") (name "/LED_WDA") (class "Default")
      (node (ref "J500") (pin "20") (pinfunction "20_20") (pintype "passive"))
      (node (ref "R515") (pin "2") (pinfunction "2_2") (pintype "passive"))
      (node (ref "TP510") (pin "1") (pinfunction "TP_1") (pintype "passive"))
    )
    (net (code "12") (name "/SEG0") (class "Default")
      (node (ref "DS500") (pin "35") (pinfunction "1A_35") (pintype "passive"))
      (node (ref "IC501") (pin "18") (pinfunction "SEG0_18") (pintype "passive"))
    )
    (net (code "13") (name "/SEG1") (class "Default")
      (node (ref "DS500") (pin "34") (pinfunction "1B_34") (pintype "passive"))
      (node (ref "IC501") (pin "19") (pinfunction "SEG1_19") (pintype "passive"))
    )
    (net (code "14") (name "/SEG2") (class "Default")
      (node (ref "DS500") (pin "7") (pinfunction "1C_7") (pintype "passive"))
      (node (ref "IC501") (pin "20") (pinfunction "SEG2_20") (pintype "passive"))
    )
    (net (code "15") (name "/SEG3") (class "Default")
      (node (ref "DS500") (pin "6") (pinfunction "1D_6") (pintype "passive"))
      (node (ref "IC501") (pin "21") (pinfunction "SEG3_21") (pintype "passive"))
    )
    (net (code "16") (name "/SEG4") (class "Default")
      (node (ref "DS500") (pin "5") (pinfunction "1E_5") (pintype "passive"))
      (node (ref "IC501") (pin "22") (pinfunction "SEG4_22") (pintype "passive"))
    )
    (net (code "17") (name "/SEG5") (class "Default")
      (node (ref "DS500") (pin "36") (pinfunction "1F_36") (pintype "passive"))
      (node (ref "IC501") (pin "23") (pinfunction "SEG5_23") (pintype "passive"))
    )
    (net (code "18") (name "/SEG6") (class "Default")
      (node (ref "DS500") (pin "37") (pinfunction "1G_37") (pintype "passive"))
      (node (ref "IC501") (pin "24") (pinfunction "SEG6_24") (pintype "passive"))
    )
    (net (code "19") (name "/SEG7") (class "Default")
      (node (ref "DS500") (pin "8") (pinfunction "DP1_8") (pintype "passive"))
      (node (ref "IC501") (pin "25") (pinfunction "SEG7_25") (pintype "passive"))
    )
    (net (code "20") (name "/SEG8") (class "Default")
      (node (ref "DS500") (pin "30") (pinfunction "2A_30") (pintype "passive"))
      (node (ref "IC501") (pin "26") (pinfunction "SEG8_26") (pintype "passive"))
    )
    (net (code "21") (name "/SEG9") (class "Default")
      (node (ref "DS500") (pin "29") (pinfunction "2B_29") (pintype "passive"))
      (node (ref "IC501") (pin "27") (pinfunction "SEG9_27") (pintype "passive"))
    )
    (net (code "22") (name "/SEG10") (class "Default")
      (node (ref "DS500") (pin "11") (pinfunction "2C_11") (pintype "passive"))
      (node (ref "IC501") (pin "28") (pinfunction "SEG10_28") (pintype "passive"))
    )
    (net (code "23") (name "/SEG11") (class "Default")
      (node (ref "DS500") (pin "10") (pinfunction "2D_10") (pintype "passive"))
      (node (ref "IC501") (pin "29") (pinfunction "SEG11_29") (pintype "passive"))
    )
    (net (code "24") (name "/SEG12") (class "Default")
      (node (ref "DS500") (pin "9") (pinfunction "2E_9") (pintype "passive"))
      (node (ref "IC501") (pin "30") (pinfunction "SEG12_30") (pintype "passive"))
    )
    (net (code "25") (name "/SEG13") (class "Default")
      (node (ref "DS500") (pin "31") (pinfunction "2F_31") (pintype "passive"))
      (node (ref "IC501") (pin "31") (pinfunction "SEG13_31") (pintype "passive"))
    )
    (net (code "26") (name "/SEG14") (class "Default")
      (node (ref "DS500") (pin "32") (pinfunction "2G_32") (pintype "passive"))
      (node (ref "IC501") (pin "32") (pinfunction "SEG14_32") (pintype "passive"))
    )
    (net (code "27") (name "/SEG15") (class "Default")
      (node (ref "DS500") (pin "12") (pinfunction "DP2_12") (pintype "passive"))
      (node (ref "IC501") (pin "33") (pinfunction "SEG15_33") (pintype "passive"))
    )
    (net (code "28") (name "/SEG16") (class "Default")
      (node (ref "DS500") (pin "25") (pinfunction "3A_25") (pintype "passive"))
      (node (ref "IC501") (pin "34") (pinfunction "SEG16_34") (pintype "passive"))
    )
    (net (code "29") (name "/SEG17") (class "Default")
      (node (ref "DS500") (pin "24") (pinfunction "3B_24") (pintype "passive"))
      (node (ref "IC501") (pin "35") (pinfunction "SEG17_35") (pintype "passive"))
    )
    (net (code "30") (name "/SEG18") (class "Default")
      (node (ref "DS500") (pin "15") (pinfunction "3C_15") (pintype "passive"))
      (node (ref "IC501") (pin "36") (pinfunction "SEG18_36") (pintype "passive"))
    )
    (net (code "31") (name "/SEG19") (class "Default")
      (node (ref "DS500") (pin "14") (pinfunction "3D_14") (pintype "passive"))
      (node (ref "IC501") (pin "37") (pinfunction "SEG19_37") (pintype "passive"))
    )
    (net (code "32") (name "/SEG20") (class "Default")
      (node (ref "DS500") (pin "13") (pinfunction "3E_13") (pintype "passive"))
      (node (ref "IC501") (pin "38") (pinfunction "SEG20_38") (pintype "passive"))
    )
    (net (code "33") (name "/SEG21") (class "Default")
      (node (ref "DS500") (pin "26") (pinfunction "3F_26") (pintype "passive"))
      (node (ref "IC501") (pin "39") (pinfunction "SEG21_39") (pintype "passive"))
    )
    (net (code "34") (name "/SEG22") (class "Default")
      (node (ref "DS500") (pin "27") (pinfunction "3G_27") (pintype "passive"))
      (node (ref "IC501") (pin "40") (pinfunction "SEG22_40") (pintype "passive"))
    )
    (net (code "35") (name "/SEG23") (class "Default")
      (node (ref "DS500") (pin "16") (pinfunction "DP3_16") (pintype "passive"))
      (node (ref "IC501") (pin "41") (pinfunction "SEG23_41") (pintype "passive"))
    )
    (net (code "36") (name "/SEG24") (class "Default")
      (node (ref "DS500") (pin "21") (pinfunction "4A_21") (pintype "passive"))
      (node (ref "IC501") (pin "42") (pinfunction "SEG24_42") (pintype "passive"))
    )
    (net (code "37") (name "/SEG25") (class "Default")
      (node (ref "DS500") (pin "20") (pinfunction "4B_20") (pintype "passive"))
      (node (ref "IC501") (pin "43") (pinfunction "SEG25_43") (pintype "passive"))
    )
    (net (code "38") (name "/SEG26") (class "Default")
      (node (ref "DS500") (pin "19") (pinfunction "4C_19") (pintype "passive"))
      (node (ref "IC501") (pin "44") (pinfunction "SEG26_44") (pintype "passive"))
    )
    (net (code "39") (name "/SEG27") (class "Default")
      (node (ref "DS500") (pin "18") (pinfunction "4D_18") (pintype "passive"))
      (node (ref "IC501") (pin "45") (pinfunction "SEG27_45") (pintype "passive"))
    )
    (net (code "40") (name "/SEG28") (class "Default")
      (node (ref "DS500") (pin "17") (pinfunction "4E_17") (pintype "passive"))
      (node (ref "IC501") (pin "46") (pinfunction "SEG28_46") (pintype "passive"))
    )
    (net (code "41") (name "/SEG29") (class "Default")
      (node (ref "DS500") (pin "22") (pinfunction "4F_22") (pintype "passive"))
      (node (ref "IC501") (pin "47") (pinfunction "SEG29_47") (pintype "passive"))
    )
    (net (code "42") (name "/SEG30") (class "Default")
      (node (ref "DS500") (pin "23") (pinfunction "4G_23") (pintype "passive"))
      (node (ref "IC501") (pin "48") (pinfunction "SEG30_48") (pintype "passive"))
    )
    (net (code "43") (name "/SEG31") (class "Default")
      (node (ref "DS500") (pin "28") (pinfunction "COL_28") (pintype "passive"))
      (node (ref "IC501") (pin "1") (pinfunction "SEG31_1") (pintype "passive"))
    )
    (net (code "44") (name "/VLCD_int") (class "Default")
      (node (ref "IC501") (pin "10") (pinfunction "VLCD_10") (pintype "passive"))
      (node (ref "R502") (pin "1") (pinfunction "1_1") (pintype "passive"))
      (node (ref "R505") (pin "2") (pinfunction "2_2") (pintype "passive"))
      (node (ref "TP514") (pin "1") (pinfunction "TP_1") (pintype "passive"))
    )
    (net (code "45") (name "/nSW_OTA") (class "Default")
      (node (ref "J500") (pin "14") (pinfunction "14_14") (pintype "passive"))
      (node (ref "SW501") (pin "1") (pinfunction "1_1") (pintype "passive"))
      (node (ref "TP503") (pin "1") (pinfunction "TP_1") (pintype "passive"))
    )
    (net (code "46") (name "/nSW_TIMER1") (class "Default")
      (node (ref "J500") (pin "12") (pinfunction "12_12") (pintype "passive"))
      (node (ref "SW503") (pin "1") (pinfunction "1_1") (pintype "passive"))
      (node (ref "TP501") (pin "1") (pinfunction "TP_1") (pintype "passive"))
    )
    (net (code "47") (name "/nSW_TIMER2") (class "Default")
      (node (ref "J500") (pin "11") (pinfunction "11_11") (pintype "passive"))
      (node (ref "SW504") (pin "1") (pinfunction "1_1") (pintype "passive"))
      (node (ref "TP500") (pin "1") (pinfunction "TP_1") (pintype "passive"))
    )
    (net (code "48") (name "/nSW_TIME_DATE") (class "Default")
      (node (ref "J500") (pin "13") (pinfunction "13_13") (pintype "passive"))
      (node (ref "SW502") (pin "1") (pinfunction "1_1") (pintype "passive"))
      (node (ref "TP502") (pin "1") (pinfunction "TP_1") (pintype "passive"))
    )
    (net (code "49") (name "/nSW_WDA") (class "Default")
      (node (ref "J500") (pin "15") (pinfunction "15_15") (pintype "passive"))
      (node (ref "SW500") (pin "1") (pinfunction "1_1") (pintype "passive"))
      (node (ref "TP504") (pin "1") (pinfunction "TP_1") (pintype "passive"))
    )
    (net (code "50") (name "3V0") (class "Default")
      (node (ref "C500") (pin "2") (pinfunction "2_2") (pintype "passive"))
      (node (ref "C501") (pin "2") (pinfunction "2_2") (pintype "passive"))
      (node (ref "C502") (pin "2") (pinfunction "2_2") (pintype "passive"))
      (node (ref "C503") (pin "2") (pinfunction "2_2") (pintype "passive"))
      (node (ref "C504") (pin "2") (pinfunction "2_2") (pintype "passive"))
      (node (ref "C505") (pin "2") (pinfunction "2_2") (pintype "passive"))
      (node (ref "C506") (pin "2") (pinfunction "2_2") (pintype "passive"))
      (node (ref "C507") (pin "2") (pinfunction "2_2") (pintype "passive"))
      (node (ref "IC500") (pin "1") (pinfunction "VIN_1") (pintype "passive"))
      (node (ref "IC502") (pin "1") (pinfunction "VIN_1") (pintype "passive"))
      (node (ref "IC503") (pin "1") (pinfunction "VDD_1") (pintype "passive"))
      (node (ref "IC504") (pin "1") (pinfunction "VDD_1") (pintype "passive"))
      (node (ref "IC505") (pin "1") (pinfunction "VDD_1") (pintype "passive"))
      (node (ref "J500") (pin "6") (pinfunction "6_6") (pintype "passive"))
      (node (ref "TP513") (pin "1") (pinfunction "TP_1") (pintype "passive"))
    )
    (net (code "51") (name "GND_LCD") (class "Default")
      (node (ref "C500") (pin "1") (pinfunction "1_1") (pintype "passive"))
      (node (ref "C501") (pin "1") (pinfunction "1_1") (pintype "passive"))
      (node (ref "C502") (pin "1") (pinfunction "1_1") (pintype "passive"))
      (node (ref "C503") (pin "1") (pinfunction "1_1") (pintype "passive"))
      (node (ref "C504") (pin "1") (pinfunction "1_1") (pintype "passive"))
      (node (ref "C505") (pin "1") (pinfunction "1_1") (pintype "passive"))
      (node (ref "C506") (pin "1") (pinfunction "1_1") (pintype "passive"))
      (node (ref "C507") (pin "1") (pinfunction "1_1") (pintype "passive"))
      (node (ref "D504") (pin "K") (pinfunction "K_K") (pintype "passive"))
      (node (ref "D505") (pin "K") (pinfunction "K_K") (pintype "passive"))
      (node (ref "D506") (pin "K") (pinfunction "K_K") (pintype "passive"))
      (node (ref "D507") (pin "K") (pinfunction "K_K") (pintype "passive"))
      (node (ref "D508") (pin "K") (pinfunction "K_K") (pintype "passive"))
      (node (ref "IC500") (pin "4") (pinfunction "GND_4") (pintype "passive"))
      (node (ref "IC500") (pin "EP") (pinfunction "EP_EP") (pintype "passive"))
      (node (ref "IC501") (pin "12") (pinfunction "VSS_12") (pintype "passive"))
      (node (ref "IC501") (pin "14") (pinfunction "OSCIO_14") (pintype "passive"))
      (node (ref "IC502") (pin "4") (pinfunction "GND_4") (pintype "passive"))
      (node (ref "IC502") (pin "EP") (pinfunction "EP_EP") (pintype "passive"))
      (node (ref "IC503") (pin "8") (pinfunction "GND_8") (pintype "passive"))
      (node (ref "IC504") (pin "8") (pinfunction "GND_8") (pintype "passive"))
      (node (ref "IC505") (pin "8") (pinfunction "GND_8") (pintype "passive"))
      (node (ref "J500") (pin "21") (pinfunction "21_21") (pintype "passive"))
      (node (ref "J500") (pin "22") (pinfunction "22_22") (pintype "passive"))
      (node (ref "J500") (pin "23") (pinfunction "23_23") (pintype "passive"))
      (node (ref "J500") (pin "24") (pinfunction "24_24") (pintype "passive"))
      (node (ref "J500") (pin "EP") (pinfunction "EP_EP") (pintype "passive"))
      (node (ref "R501") (pin "1") (pinfunction "1_1") (pintype "passive"))
      (node (ref "R504") (pin "1") (pinfunction "1_1") (pintype "passive"))
      (node (ref "R505") (pin "1") (pinfunction "1_1") (pintype "passive"))
      (node (ref "R506") (pin "2") (pinfunction "2_2") (pintype "passive"))
      (node (ref "R507") (pin "2") (pinfunction "2_2") (pintype "passive"))
      (node (ref "R508") (pin "2") (pinfunction "2_2") (pintype "passive"))
      (node (ref "R509") (pin "2") (pinfunction "2_2") (pintype "passive"))
      (node (ref "R510") (pin "2") (pinfunction "2_2") (pintype "passive"))
      (node (ref "R518") (pin "1") (pinfunction "1_1") (pintype "passive"))
      (node (ref "R519") (pin "1") (pinfunction "1_1") (pintype "passive"))
      (node (ref "R520") (pin "1") (pinfunction "1_1") (pintype "passive"))
      (node (ref "SW500") (pin "4") (pinfunction "4_4") (pintype "passive"))
      (node (ref "SW501") (pin "4") (pinfunction "4_4") (pintype "passive"))
      (node (ref "SW502") (pin "4") (pinfunction "4_4") (pintype "passive"))
      (node (ref "SW503") (pin "4") (pinfunction "4_4") (pintype "passive"))
      (node (ref "SW504") (pin "4") (pinfunction "4_4") (pintype "passive"))
      (node (ref "TP519") (pin "1") (pinfunction "TP_1") (pintype "passive"))
    )
    (net (code "52") (name "LCD_EP") (class "Default")
      (node (ref "D513") (pin "EP") (pinfunction "EP_EP") (pintype "passive"))
      (node (ref "D514") (pin "EP") (pinfunction "EP_EP") (pintype "passive"))
      (node (ref "D515") (pin "EP") (pinfunction "EP_EP") (pintype "passive"))
      (node (ref "HS500") (pin "EP") (pinfunction "EP_EP") (pintype "passive"))
      (node (ref "HS501") (pin "EP") (pinfunction "EP_EP") (pintype "passive"))
      (node (ref "HS502") (pin "EP") (pinfunction "EP_EP") (pintype "passive"))
    )
    (net (code "53") (name "Net-(D500-K)") (class "Default")
      (node (ref "D500") (pin "1") (pinfunction "K_1") (pintype "passive"))
      (node (ref "IC500") (pin "10") (pinfunction "D1_10") (pintype "passive"))
    )
    (net (code "54") (name "Net-(D501-K)") (class "Default")
      (node (ref "D501") (pin "1") (pinfunction "K_1") (pintype "passive"))
      (node (ref "IC500") (pin "9") (pinfunction "D2_9") (pintype "passive"))
    )
    (net (code "55") (name "Net-(D502-K)") (class "Default")
      (node (ref "D502") (pin "1") (pinfunction "K_1") (pintype "passive"))
      (node (ref "IC500") (pin "8") (pinfunction "D3_8") (pintype "passive"))
    )
    (net (code "56") (name "Net-(D503-K)") (class "Default")
      (node (ref "D503") (pin "1") (pinfunction "K_1") (pintype "passive"))
      (node (ref "IC500") (pin "7") (pinfunction "D4_7") (pintype "passive"))
    )
    (net (code "57") (name "Net-(D504-PadA)") (class "Default")
      (node (ref "D504") (pin "A") (pinfunction "A_A") (pintype "passive"))
      (node (ref "R515") (pin "1") (pinfunction "1_1") (pintype "passive"))
    )
    (net (code "58") (name "Net-(D505-PadA)") (class "Default")
      (node (ref "D505") (pin "A") (pinfunction "A_A") (pintype "passive"))
      (node (ref "R514") (pin "1") (pinfunction "1_1") (pintype "passive"))
    )
    (net (code "59") (name "Net-(D506-PadA)") (class "Default")
      (node (ref "D506") (pin "A") (pinfunction "A_A") (pintype "passive"))
      (node (ref "R513") (pin "1") (pinfunction "1_1") (pintype "passive"))
    )
    (net (code "60") (name "Net-(D507-PadA)") (class "Default")
      (node (ref "D507") (pin "A") (pinfunction "A_A") (pintype "passive"))
      (node (ref "R512") (pin "1") (pinfunction "1_1") (pintype "passive"))
    )
    (net (code "61") (name "Net-(D508-PadA)") (class "Default")
      (node (ref "D508") (pin "A") (pinfunction "A_A") (pintype "passive"))
      (node (ref "R511") (pin "1") (pinfunction "1_1") (pintype "passive"))
    )
    (net (code "62") (name "Net-(D509-K)") (class "Default")
      (node (ref "D509") (pin "1") (pinfunction "K_1") (pintype "passive"))
      (node (ref "IC502") (pin "10") (pinfunction "D1_10") (pintype "passive"))
      (node (ref "TP512") (pin "1") (pinfunction "TP_1") (pintype "passive"))
    )
    (net (code "63") (name "Net-(D510-K)") (class "Default")
      (node (ref "D510") (pin "1") (pinfunction "K_1") (pintype "passive"))
      (node (ref "IC502") (pin "9") (pinfunction "D2_9") (pintype "passive"))
    )
    (net (code "64") (name "Net-(D511-K)") (class "Default")
      (node (ref "D511") (pin "1") (pinfunction "K_1") (pintype "passive"))
      (node (ref "IC502") (pin "8") (pinfunction "D3_8") (pintype "passive"))
    )
    (net (code "65") (name "Net-(D512-K)") (class "Default")
      (node (ref "D512") (pin "1") (pinfunction "K_1") (pintype "passive"))
      (node (ref "IC502") (pin "7") (pinfunction "D4_7") (pintype "passive"))
    )
    (net (code "66") (name "Net-(IC500-RSET)") (class "Default")
      (node (ref "IC500") (pin "3") (pinfunction "RSET_3") (pintype "passive"))
      (node (ref "R500") (pin "1") (pinfunction "1_1") (pintype "passive"))
    )
    (net (code "67") (name "Net-(IC501-SCL)") (class "Default")
      (node (ref "IC501") (pin "15") (pinfunction "SCL_15") (pintype "passive"))
      (node (ref "R516") (pin "1") (pinfunction "1_1") (pintype "passive"))
      (node (ref "TP517") (pin "1") (pinfunction "TP_1") (pintype "passive"))
    )
    (net (code "68") (name "Net-(IC501-SDA)") (class "Default")
      (node (ref "IC501") (pin "16") (pinfunction "SDA_16") (pintype "passive"))
      (node (ref "R517") (pin "1") (pinfunction "1_1") (pintype "passive"))
      (node (ref "TP518") (pin "1") (pinfunction "TP_1") (pintype "passive"))
    )
    (net (code "69") (name "Net-(IC501-TEST1)") (class "Default")
      (node (ref "IC501") (pin "13") (pinfunction "TEST1_13") (pintype "passive"))
      (node (ref "R507") (pin "1") (pinfunction "1_1") (pintype "passive"))
    )
    (net (code "70") (name "Net-(IC501-TEST2)") (class "Default")
      (node (ref "IC501") (pin "17") (pinfunction "TEST2_17") (pintype "passive"))
      (node (ref "R508") (pin "1") (pinfunction "1_1") (pintype "passive"))
    )
    (net (code "71") (name "Net-(IC502-RSET)") (class "Default")
      (node (ref "IC502") (pin "3") (pinfunction "RSET_3") (pintype "passive"))
      (node (ref "R503") (pin "1") (pinfunction "1_1") (pintype "passive"))
    )
    (net (code "72") (name "Net-(IC503-CS-Pad5)") (class "Default")
      (node (ref "IC503") (pin "5") (pinfunction "CS_5") (pintype "passive"))
      (node (ref "IC503") (pin "6") (pinfunction "CS_6") (pintype "passive"))
      (node (ref "R506") (pin "1") (pinfunction "1_1") (pintype "passive"))
    )
    (net (code "73") (name "Net-(IC503-LED)") (class "Default")
      (node (ref "D513") (pin "K") (pinfunction "K_K") (pintype "passive"))
      (node (ref "IC503") (pin "4") (pinfunction "LED_4") (pintype "passive"))
      (node (ref "IC503") (pin "EP") (pinfunction "EP_EP") (pintype "passive"))
      (node (ref "TP516") (pin "1") (pinfunction "TP_1") (pintype "passive"))
    )
    (net (code "74") (name "Net-(IC504-CS-Pad5)") (class "Default")
      (node (ref "IC504") (pin "5") (pinfunction "CS_5") (pintype "passive"))
      (node (ref "IC504") (pin "6") (pinfunction "CS_6") (pintype "passive"))
      (node (ref "R509") (pin "1") (pinfunction "1_1") (pintype "passive"))
    )
    (net (code "75") (name "Net-(IC504-LED)") (class "Default")
      (node (ref "D514") (pin "K") (pinfunction "K_K") (pintype "passive"))
      (node (ref "IC504") (pin "4") (pinfunction "LED_4") (pintype "passive"))
      (node (ref "IC504") (pin "EP") (pinfunction "EP_EP") (pintype "passive"))
      (node (ref "TP520") (pin "1") (pinfunction "TP_1") (pintype "passive"))
    )
    (net (code "76") (name "Net-(IC505-CS-Pad5)") (class "Default")
      (node (ref "IC505") (pin "5") (pinfunction "CS_5") (pintype "passive"))
      (node (ref "IC505") (pin "6") (pinfunction "CS_6") (pintype "passive"))
      (node (ref "R510") (pin "1") (pinfunction "1_1") (pintype "passive"))
    )
    (net (code "77") (name "Net-(IC505-LED)") (class "Default")
      (node (ref "D515") (pin "K") (pinfunction "K_K") (pintype "passive"))
      (node (ref "IC505") (pin "4") (pinfunction "LED_4") (pintype "passive"))
      (node (ref "IC505") (pin "EP") (pinfunction "EP_EP") (pintype "passive"))
      (node (ref "TP521") (pin "1") (pinfunction "TP_1") (pintype "passive"))
    )
    (net (code "78") (name "Net-(R500-Pad2)") (class "Default")
      (node (ref "R500") (pin "2") (pinfunction "2_2") (pintype "passive"))
      (node (ref "R501") (pin "2") (pinfunction "2_2") (pintype "passive"))
    )
    (net (code "79") (name "Net-(R503-Pad2)") (class "Default")
      (node (ref "R503") (pin "2") (pinfunction "2_2") (pintype "passive"))
      (node (ref "R504") (pin "2") (pinfunction "2_2") (pintype "passive"))
    )
    (net (code "80") (name "VBAT") (class "Default")
      (node (ref "D500") (pin "2") (pinfunction "A_2") (pintype "passive"))
      (node (ref "D501") (pin "2") (pinfunction "A_2") (pintype "passive"))
      (node (ref "D502") (pin "2") (pinfunction "A_2") (pintype "passive"))
      (node (ref "D503") (pin "2") (pinfunction "A_2") (pintype "passive"))
      (node (ref "D509") (pin "2") (pinfunction "A_2") (pintype "passive"))
      (node (ref "D510") (pin "2") (pinfunction "A_2") (pintype "passive"))
      (node (ref "D511") (pin "2") (pinfunction "A_2") (pintype "passive"))
      (node (ref "D512") (pin "2") (pinfunction "A_2") (pintype "passive"))
      (node (ref "IC501") (pin "11") (pinfunction "VDD_11") (pintype "passive"))
      (node (ref "J500") (pin "5") (pinfunction "5_5") (pintype "passive"))
      (node (ref "R502") (pin "2") (pinfunction "2_2") (pintype "passive"))
      (node (ref "TP505") (pin "1") (pinfunction "TP_1") (pintype "passive"))
    )
    (net (code "81") (name "VLED") (class "Default")
      (node (ref "D513") (pin "A") (pinfunction "A_A") (pintype "passive"))
      (node (ref "D514") (pin "A") (pinfunction "A_A") (pintype "passive"))
      (node (ref "D515") (pin "A") (pinfunction "A_A") (pintype "passive"))
      (node (ref "J500") (pin "1") (pinfunction "1_1") (pintype "passive"))
      (node (ref "J500") (pin "2") (pinfunction "2_2") (pintype "passive"))
      (node (ref "J500") (pin "3") (pinfunction "3_3") (pintype "passive"))
      (node (ref "TP522") (pin "1") (pinfunction "TP_1") (pintype "passive"))
    )
    (net (code "82") (name "unconnected-(DS500-N.C.-Pad2)") (class "Default")
      (node (ref "DS500") (pin "2") (pinfunction "N.C._2") (pintype "passive+no_connect"))
    )
    (net (code "83") (name "unconnected-(DS500-N.C.-Pad3)") (class "Default")
      (node (ref "DS500") (pin "3") (pinfunction "N.C._3") (pintype "passive+no_connect"))
    )
    (net (code "84") (name "unconnected-(DS500-N.C.-Pad4)") (class "Default")
      (node (ref "DS500") (pin "4") (pinfunction "N.C._4") (pintype "passive+no_connect"))
    )
    (net (code "85") (name "unconnected-(DS500-N.C.-Pad33)") (class "Default")
      (node (ref "DS500") (pin "33") (pinfunction "N.C._33") (pintype "passive+no_connect"))
    )
    (net (code "86") (name "unconnected-(DS500-N.C.-Pad38)") (class "Default")
      (node (ref "DS500") (pin "38") (pinfunction "N.C._38") (pintype "passive+no_connect"))
    )
    (net (code "87") (name "unconnected-(DS500-N.C.-Pad39)") (class "Default")
      (node (ref "DS500") (pin "39") (pinfunction "N.C._39") (pintype "passive+no_connect"))
    )
    (net (code "88") (name "unconnected-(FIDJ100-Pad1)") (class "Default")
      (node (ref "FIDJ100") (pin "1") (pinfunction "1_1") (pintype "passive"))
    )
    (net (code "89") (name "unconnected-(FIDJ101-Pad1)") (class "Default")
      (node (ref "FIDJ101") (pin "1") (pinfunction "1_1") (pintype "passive"))
    )
    (net (code "90") (name "unconnected-(IC501-COM1-Pad7)") (class "Default")
      (node (ref "IC501") (pin "7") (pinfunction "COM1_7") (pintype "passive+no_connect"))
    )
    (net (code "91") (name "unconnected-(IC501-COM2-Pad8)") (class "Default")
      (node (ref "IC501") (pin "8") (pinfunction "COM2_8") (pintype "passive+no_connect"))
    )
    (net (code "92") (name "unconnected-(IC501-COM3-Pad9)") (class "Default")
      (node (ref "IC501") (pin "9") (pinfunction "COM3_9") (pintype "passive+no_connect"))
    )
    (net (code "93") (name "unconnected-(IC501-SEG32-Pad2)") (class "Default")
      (node (ref "IC501") (pin "2") (pinfunction "SEG32_2") (pintype "passive+no_connect"))
    )
    (net (code "94") (name "unconnected-(IC501-SEG33-Pad3)") (class "Default")
      (node (ref "IC501") (pin "3") (pinfunction "SEG33_3") (pintype "passive+no_connect"))
    )
    (net (code "95") (name "unconnected-(IC501-SEG34-Pad4)") (class "Default")
      (node (ref "IC501") (pin "4") (pinfunction "SEG34_4") (pintype "passive+no_connect"))
    )
    (net (code "96") (name "unconnected-(IC501-SEG35-Pad5)") (class "Default")
      (node (ref "IC501") (pin "5") (pinfunction "SEG35_5") (pintype "passive+no_connect"))
    )
    (net (code "97") (name "unconnected-(IC503-NC-Pad3)") (class "Default")
      (node (ref "IC503") (pin "3") (pinfunction "NC_3") (pintype "passive+no_connect"))
    )
    (net (code "98") (name "unconnected-(IC503-NC-Pad7)") (class "Default")
      (node (ref "IC503") (pin "7") (pinfunction "NC_7") (pintype "passive+no_connect"))
    )
    (net (code "99") (name "unconnected-(IC504-NC-Pad3)") (class "Default")
      (node (ref "IC504") (pin "3") (pinfunction "NC_3") (pintype "passive+no_connect"))
    )
    (net (code "100") (name "unconnected-(IC504-NC-Pad7)") (class "Default")
      (node (ref "IC504") (pin "7") (pinfunction "NC_7") (pintype "passive+no_connect"))
    )
    (net (code "101") (name "unconnected-(IC505-NC-Pad3)") (class "Default")
      (node (ref "IC505") (pin "3") (pinfunction "NC_3") (pintype "passive+no_connect"))
    )
    (net (code "102") (name "unconnected-(IC505-NC-Pad7)") (class "Default")
      (node (ref "IC505") (pin "7") (pinfunction "NC_7") (pintype "passive+no_connect"))
    )
    (net (code "103") (name "unconnected-(SW500-Pad2)") (class "Default")
      (node (ref "SW500") (pin "2") (pinfunction "2_2") (pintype "passive"))
    )
    (net (code "104") (name "unconnected-(SW500-Pad3)") (class "Default")
      (node (ref "SW500") (pin "3") (pinfunction "3_3") (pintype "passive"))
    )
    (net (code "105") (name "unconnected-(SW501-Pad2)") (class "Default")
      (node (ref "SW501") (pin "2") (pinfunction "2_2") (pintype "passive"))
    )
    (net (code "106") (name "unconnected-(SW501-Pad3)") (class "Default")
      (node (ref "SW501") (pin "3") (pinfunction "3_3") (pintype "passive"))
    )
    (net (code "107") (name "unconnected-(SW502-Pad2)") (class "Default")
      (node (ref "SW502") (pin "2") (pinfunction "2_2") (pintype "passive"))
    )
    (net (code "108") (name "unconnected-(SW502-Pad3)") (class "Default")
      (node (ref "SW502") (pin "3") (pinfunction "3_3") (pintype "passive"))
    )
    (net (code "109") (name "unconnected-(SW503-Pad2)") (class "Default")
      (node (ref "SW503") (pin "2") (pinfunction "2_2") (pintype "passive"))
    )
    (net (code "110") (name "unconnected-(SW503-Pad3)") (class "Default")
      (node (ref "SW503") (pin "3") (pinfunction "3_3") (pintype "passive"))
    )
    (net (code "111") (name "unconnected-(SW504-Pad2)") (class "Default")
      (node (ref "SW504") (pin "2") (pinfunction "2_2") (pintype "passive"))
    )
    (net (code "112") (name "unconnected-(SW504-Pad3)") (class "Default")
      (node (ref "SW504") (pin "3") (pinfunction "3_3") (pintype "passive"))
    )
  )
)
